# MultiTB.net
KiCad netlist of a schematic drawn in EAGLE
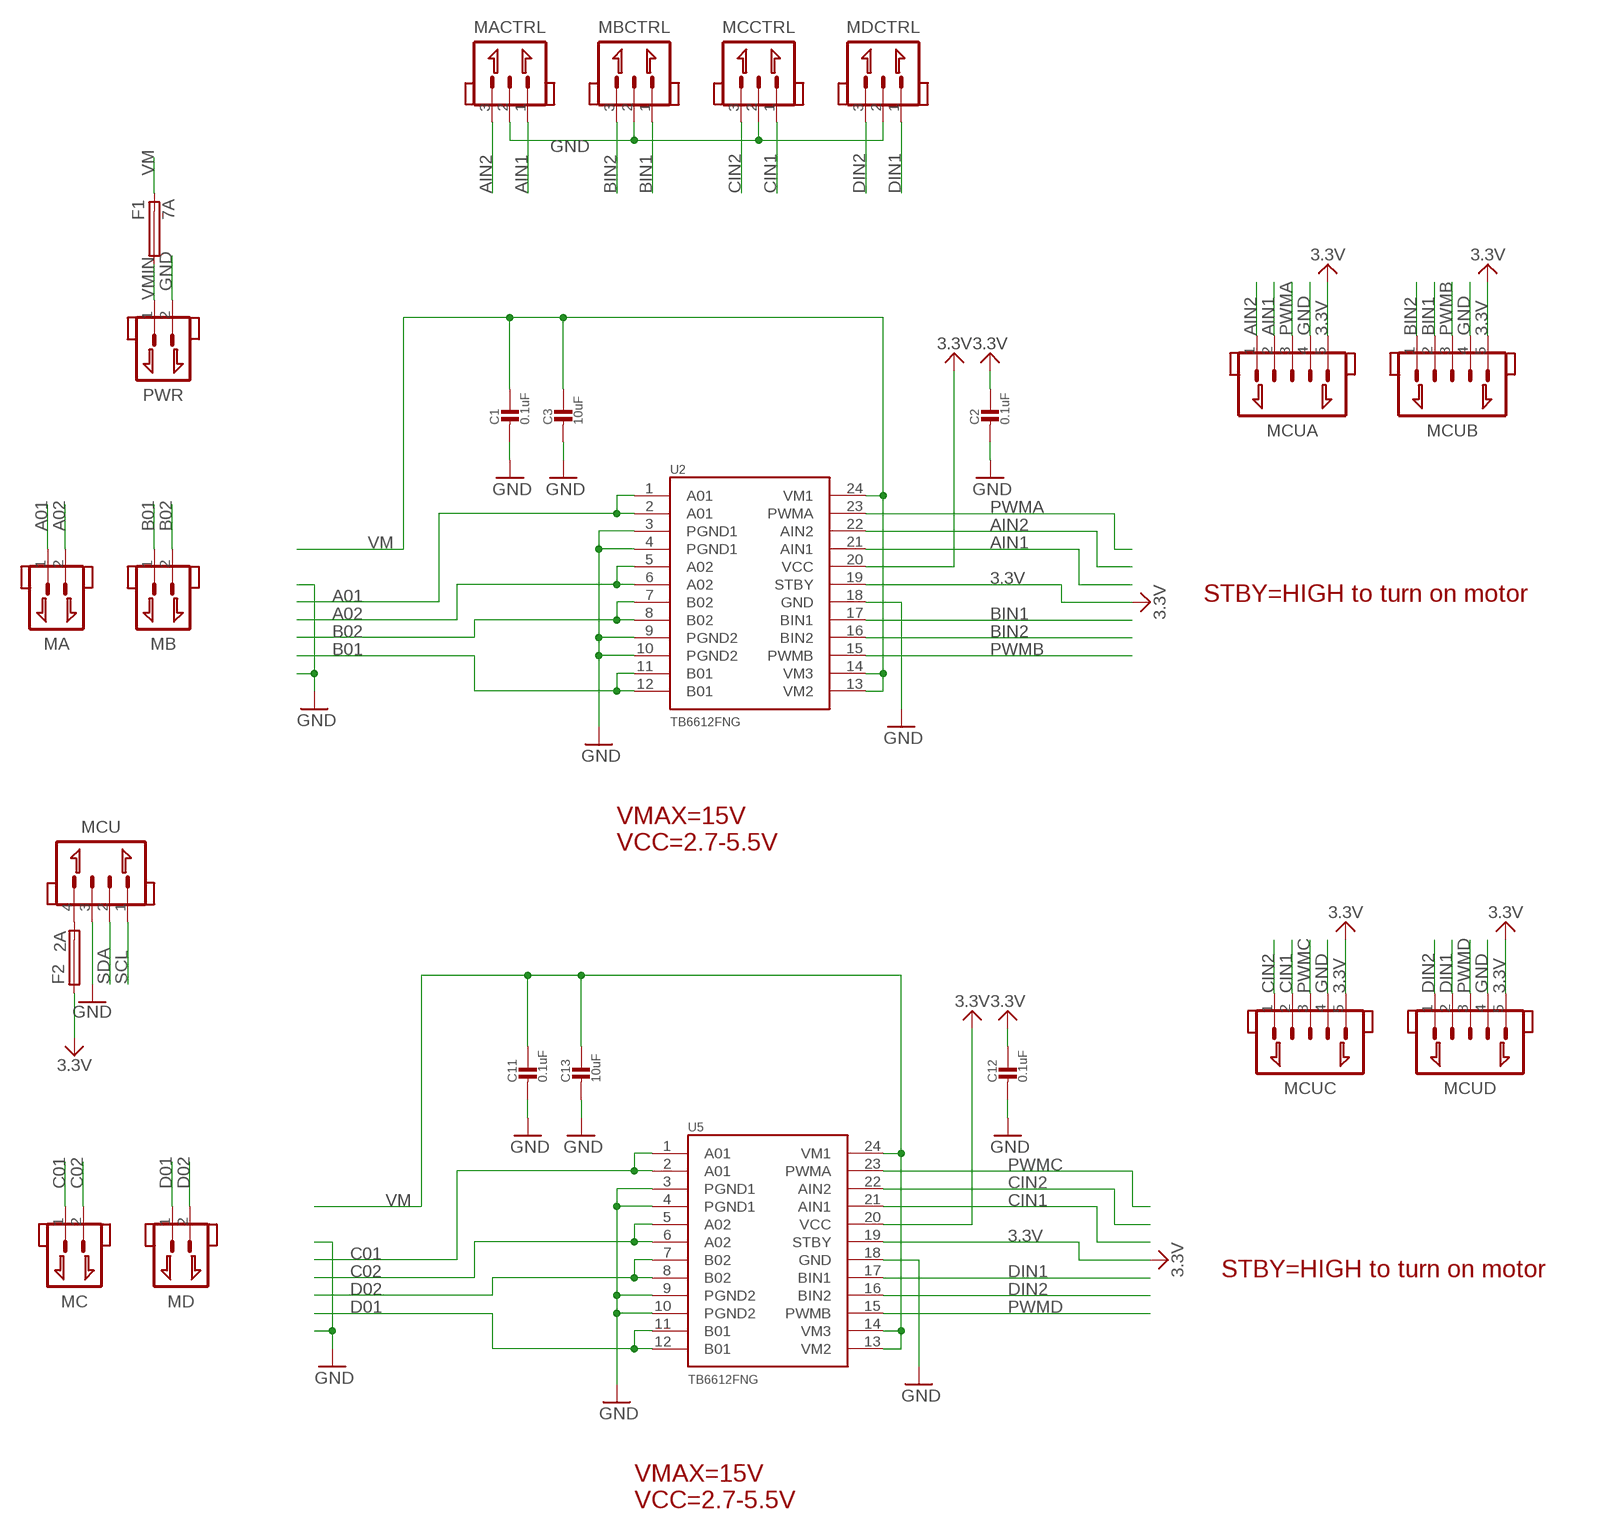
[diagram p0: schematic, sheet 1]
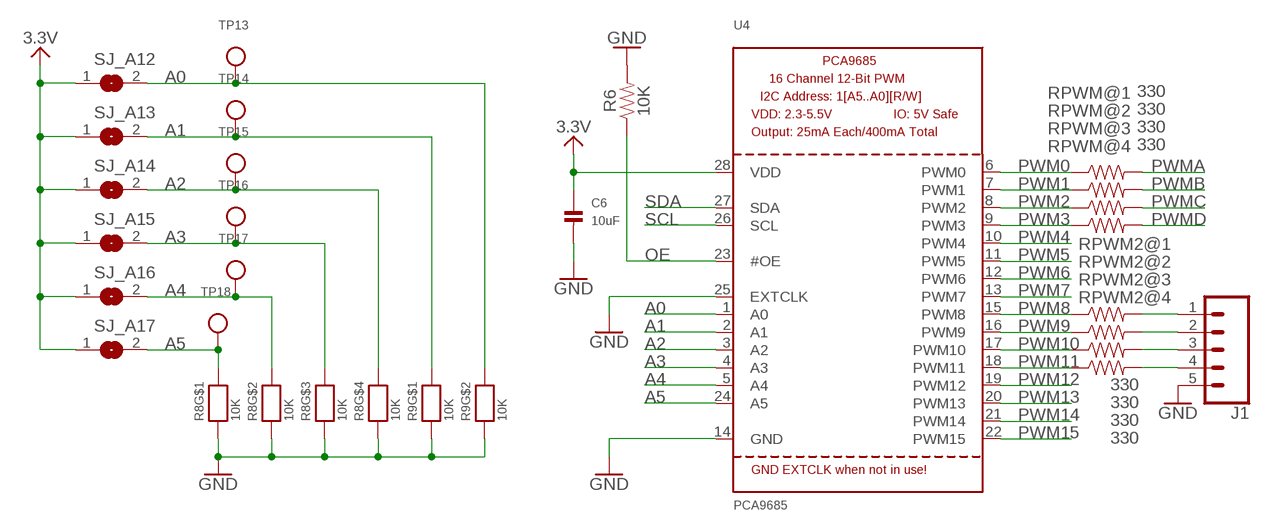
[diagram p1: schematic, sheet 2]

(export (version "E")
  (design (tool "Eeschema 10.0.6"))
  (components
    (comp (ref "C1")
      (value "0.1uF")
      (footprint "eagle-import:0603")
      (libsource (lib "eagle-import") (part "CAP_CERAMIC_0603"))
    )
    (comp (ref "C2")
      (value "0.1uF")
      (footprint "eagle-import:0603")
      (libsource (lib "eagle-import") (part "CAP_CERAMIC_0603"))
    )
    (comp (ref "C3")
      (value "10uF")
      (footprint "eagle-import:0805")
      (libsource (lib "eagle-import") (part "CAP_CERAMIC_0805"))
    )
    (comp (ref "C11")
      (value "0.1uF")
      (footprint "eagle-import:0603")
      (libsource (lib "eagle-import") (part "CAP_CERAMIC_0603"))
    )
    (comp (ref "C12")
      (value "0.1uF")
      (footprint "eagle-import:0603")
      (libsource (lib "eagle-import") (part "CAP_CERAMIC_0603"))
    )
    (comp (ref "C13")
      (value "10uF")
      (footprint "eagle-import:0805")
      (libsource (lib "eagle-import") (part "CAP_CERAMIC_0805"))
    )
    (comp (ref "F1")
      (value "7A")
      (footprint "eagle-import:1206")
      (libsource (lib "eagle-import") (part "FUSE-1206"))
    )
    (comp (ref "F2")
      (value "2A")
      (footprint "eagle-import:0603")
      (libsource (lib "eagle-import") (part "FUSE-0603"))
    )
    (comp (ref "MA")
      (value "JST_XH_2.54_2P")
      (footprint "eagle-import:JST_XH_2.54_2P")
      (libsource (lib "eagle-import") (part "JST_XH_2.54_2P"))
    )
    (comp (ref "MACTRL")
      (value "JST_1.25_3P")
      (footprint "eagle-import:JST1.25_3P")
      (libsource (lib "eagle-import") (part "JST_1.25_3P"))
    )
    (comp (ref "MB")
      (value "JST_XH_2.54_2P")
      (footprint "eagle-import:JST_XH_2.54_2P")
      (libsource (lib "eagle-import") (part "JST_XH_2.54_2P"))
    )
    (comp (ref "MBCTRL")
      (value "JST_1.25_3P")
      (footprint "eagle-import:JST1.25_3P")
      (libsource (lib "eagle-import") (part "JST_1.25_3P"))
    )
    (comp (ref "MC")
      (value "JST_XH_2.54_2P")
      (footprint "eagle-import:JST_XH_2.54_2P")
      (libsource (lib "eagle-import") (part "JST_XH_2.54_2P"))
    )
    (comp (ref "MCCTRL")
      (value "JST_1.25_3P")
      (footprint "eagle-import:JST1.25_3P")
      (libsource (lib "eagle-import") (part "JST_1.25_3P"))
    )
    (comp (ref "MCU")
      (value "JST_1.25_4P")
      (footprint "eagle-import:JST1.25_4P")
      (libsource (lib "eagle-import") (part "JST_1.25_4P"))
    )
    (comp (ref "MCUA")
      (value "JST_1.25_5P")
      (footprint "eagle-import:JST1.25_5P")
      (libsource (lib "eagle-import") (part "JST_1.25_5P"))
    )
    (comp (ref "MCUB")
      (value "JST_1.25_5P")
      (footprint "eagle-import:JST1.25_5P")
      (libsource (lib "eagle-import") (part "JST_1.25_5P"))
    )
    (comp (ref "MCUC")
      (value "JST_1.25_5P")
      (footprint "eagle-import:JST1.25_5P")
      (libsource (lib "eagle-import") (part "JST_1.25_5P"))
    )
    (comp (ref "MCUD")
      (value "JST_1.25_5P")
      (footprint "eagle-import:JST1.25_5P")
      (libsource (lib "eagle-import") (part "JST_1.25_5P"))
    )
    (comp (ref "MD")
      (value "JST_XH_2.54_2P")
      (footprint "eagle-import:JST_XH_2.54_2P")
      (libsource (lib "eagle-import") (part "JST_XH_2.54_2P"))
    )
    (comp (ref "MDCTRL")
      (value "JST_1.25_3P")
      (footprint "eagle-import:JST1.25_3P")
      (libsource (lib "eagle-import") (part "JST_1.25_3P"))
    )
    (comp (ref "PWR")
      (value "JST_XH_2.54_2P")
      (footprint "eagle-import:JST_XH_2.54_2P")
      (libsource (lib "eagle-import") (part "JST_XH_2.54_2P"))
    )
    (comp (ref "U2")
      (value "TB6612FNG")
      (footprint "eagle-import:SSOP24")
      (libsource (lib "eagle-import") (part "TB6612FNG"))
    )
    (comp (ref "U5")
      (value "TB6612FNG")
      (footprint "eagle-import:SSOP24")
      (libsource (lib "eagle-import") (part "TB6612FNG"))
    )
    (comp (ref "C6")
      (value "10uF")
      (footprint "eagle-import:0805")
      (libsource (lib "eagle-import") (part "CAP_CERAMIC_0805"))
    )
    (comp (ref "J1")
      (value "CONN_05")
      (footprint "eagle-import:1X05")
      (libsource (lib "eagle-import") (part "CONN_05"))
    )
    (comp (ref "R6")
      (value "10K")
      (footprint "eagle-import:0603")
      (libsource (lib "eagle-import") (part "RESISTOR0603"))
    )
    (comp (ref "R8")
      (value "10K")
      (footprint "eagle-import:RESPACK_4X0603")
      (libsource (lib "eagle-import") (part "RESISTOR_4PACK"))
    )
    (comp (ref "R9")
      (value "10K")
      (footprint "eagle-import:RESPACK_4X0603")
      (libsource (lib "eagle-import") (part "RESISTOR_4PACK"))
    )
    (comp (ref "RPWM")
      (value "330")
      (footprint "eagle-import:RESCAF80P320X160X60-8N")
      (libsource (lib "eagle-import") (part "RESISTOR_ARRAY_1206_SEPARATE_REVERSE"))
    )
    (comp (ref "RPWM2")
      (value "330")
      (footprint "eagle-import:RESCAF80P320X160X60-8N")
      (libsource (lib "eagle-import") (part "RESISTOR_ARRAY_1206_SEPARATE_REVERSE"))
    )
    (comp (ref "SJ_A12")
      (value "SOLDERJUMPERREFLOW_NOPASTE")
      (footprint "eagle-import:SOLDERJUMPER_REFLOW_NOPASTE")
      (libsource (lib "eagle-import") (part "SOLDERJUMPERREFLOW_NOPASTE"))
    )
    (comp (ref "SJ_A13")
      (value "SOLDERJUMPERREFLOW_NOPASTE")
      (footprint "eagle-import:SOLDERJUMPER_REFLOW_NOPASTE")
      (libsource (lib "eagle-import") (part "SOLDERJUMPERREFLOW_NOPASTE"))
    )
    (comp (ref "SJ_A14")
      (value "SOLDERJUMPERREFLOW_NOPASTE")
      (footprint "eagle-import:SOLDERJUMPER_REFLOW_NOPASTE")
      (libsource (lib "eagle-import") (part "SOLDERJUMPERREFLOW_NOPASTE"))
    )
    (comp (ref "SJ_A15")
      (value "SOLDERJUMPERREFLOW_NOPASTE")
      (footprint "eagle-import:SOLDERJUMPER_REFLOW_NOPASTE")
      (libsource (lib "eagle-import") (part "SOLDERJUMPERREFLOW_NOPASTE"))
    )
    (comp (ref "SJ_A16")
      (value "SOLDERJUMPERREFLOW_NOPASTE")
      (footprint "eagle-import:SOLDERJUMPER_REFLOW_NOPASTE")
      (libsource (lib "eagle-import") (part "SOLDERJUMPERREFLOW_NOPASTE"))
    )
    (comp (ref "SJ_A17")
      (value "SOLDERJUMPERREFLOW_NOPASTE")
      (footprint "eagle-import:SOLDERJUMPER_REFLOW_NOPASTE")
      (libsource (lib "eagle-import") (part "SOLDERJUMPERREFLOW_NOPASTE"))
    )
    (comp (ref "TP13")
      (value "TESTPOINTROUND2MM")
      (footprint "eagle-import:TESTPOINT_ROUND_2MM")
      (libsource (lib "eagle-import") (part "TESTPOINTROUND2MM"))
    )
    (comp (ref "TP14")
      (value "TESTPOINTROUND2MM")
      (footprint "eagle-import:TESTPOINT_ROUND_2MM")
      (libsource (lib "eagle-import") (part "TESTPOINTROUND2MM"))
    )
    (comp (ref "TP15")
      (value "TESTPOINTROUND2MM")
      (footprint "eagle-import:TESTPOINT_ROUND_2MM")
      (libsource (lib "eagle-import") (part "TESTPOINTROUND2MM"))
    )
    (comp (ref "TP16")
      (value "TESTPOINTROUND2MM")
      (footprint "eagle-import:TESTPOINT_ROUND_2MM")
      (libsource (lib "eagle-import") (part "TESTPOINTROUND2MM"))
    )
    (comp (ref "TP17")
      (value "TESTPOINTROUND2MM")
      (footprint "eagle-import:TESTPOINT_ROUND_2MM")
      (libsource (lib "eagle-import") (part "TESTPOINTROUND2MM"))
    )
    (comp (ref "TP18")
      (value "TESTPOINTROUND2MM")
      (footprint "eagle-import:TESTPOINT_ROUND_2MM")
      (libsource (lib "eagle-import") (part "TESTPOINTROUND2MM"))
    )
    (comp (ref "U4")
      (value "PCA9685")
      (footprint "eagle-import:TSSOP28")
      (libsource (lib "eagle-import") (part "PCA9685"))
    )
  )
  (nets
    (net (code "1") (name "3.3V") (class "Default")
      (node (ref "C12") (pin "1") (pinfunction "1_1") (pintype "passive"))
      (node (ref "C2") (pin "1") (pinfunction "1_1") (pintype "passive"))
      (node (ref "C6") (pin "1") (pinfunction "1_1") (pintype "passive"))
      (node (ref "F2") (pin "1") (pinfunction "1_1") (pintype "passive"))
      (node (ref "MCUA") (pin "5") (pinfunction "5_5") (pintype "passive"))
      (node (ref "MCUB") (pin "5") (pinfunction "5_5") (pintype "passive"))
      (node (ref "MCUC") (pin "5") (pinfunction "5_5") (pintype "passive"))
      (node (ref "MCUD") (pin "5") (pinfunction "5_5") (pintype "passive"))
      (node (ref "SJ_A12") (pin "1") (pinfunction "1_1") (pintype "passive"))
      (node (ref "SJ_A13") (pin "1") (pinfunction "1_1") (pintype "passive"))
      (node (ref "SJ_A14") (pin "1") (pinfunction "1_1") (pintype "passive"))
      (node (ref "SJ_A15") (pin "1") (pinfunction "1_1") (pintype "passive"))
      (node (ref "SJ_A16") (pin "1") (pinfunction "1_1") (pintype "passive"))
      (node (ref "SJ_A17") (pin "1") (pinfunction "1_1") (pintype "passive"))
      (node (ref "U2") (pin "19") (pinfunction "STBY_19") (pintype "bidirectional"))
      (node (ref "U2") (pin "20") (pinfunction "VCC_20") (pintype "bidirectional"))
      (node (ref "U4") (pin "28") (pinfunction "VDD_28") (pintype "power_in"))
      (node (ref "U5") (pin "19") (pinfunction "STBY_19") (pintype "bidirectional"))
      (node (ref "U5") (pin "20") (pinfunction "VCC_20") (pintype "bidirectional"))
    )
    (net (code "2") (name "A0") (class "Default")
      (node (ref "R9") (pin "7") (pinfunction "2_7") (pintype "passive"))
      (node (ref "SJ_A12") (pin "2") (pinfunction "2_2") (pintype "passive"))
      (node (ref "TP13") (pin "P$1") (pinfunction "P$1_P$1") (pintype "bidirectional"))
      (node (ref "U4") (pin "1") (pinfunction "A0_1") (pintype "bidirectional"))
    )
    (net (code "3") (name "A1") (class "Default")
      (node (ref "R9") (pin "8") (pinfunction "2_8") (pintype "passive"))
      (node (ref "SJ_A13") (pin "2") (pinfunction "2_2") (pintype "passive"))
      (node (ref "TP14") (pin "P$1") (pinfunction "P$1_P$1") (pintype "bidirectional"))
      (node (ref "U4") (pin "2") (pinfunction "A1_2") (pintype "bidirectional"))
    )
    (net (code "4") (name "A01") (class "Default")
      (node (ref "MA") (pin "1") (pinfunction "1_1") (pintype "passive"))
      (node (ref "U2") (pin "1") (pinfunction "A01_1") (pintype "bidirectional"))
      (node (ref "U2") (pin "2") (pinfunction "A01_2") (pintype "bidirectional"))
    )
    (net (code "5") (name "A2") (class "Default")
      (node (ref "R8") (pin "5") (pinfunction "2_5") (pintype "passive"))
      (node (ref "SJ_A14") (pin "2") (pinfunction "2_2") (pintype "passive"))
      (node (ref "TP15") (pin "P$1") (pinfunction "P$1_P$1") (pintype "bidirectional"))
      (node (ref "U4") (pin "3") (pinfunction "A2_3") (pintype "bidirectional"))
    )
    (net (code "6") (name "A02") (class "Default")
      (node (ref "MA") (pin "2") (pinfunction "2_2") (pintype "passive"))
      (node (ref "U2") (pin "5") (pinfunction "A02_5") (pintype "bidirectional"))
      (node (ref "U2") (pin "6") (pinfunction "A02_6") (pintype "bidirectional"))
    )
    (net (code "7") (name "A3") (class "Default")
      (node (ref "R8") (pin "6") (pinfunction "2_6") (pintype "passive"))
      (node (ref "SJ_A15") (pin "2") (pinfunction "2_2") (pintype "passive"))
      (node (ref "TP16") (pin "P$1") (pinfunction "P$1_P$1") (pintype "bidirectional"))
      (node (ref "U4") (pin "4") (pinfunction "A3_4") (pintype "bidirectional"))
    )
    (net (code "8") (name "A4") (class "Default")
      (node (ref "R8") (pin "7") (pinfunction "2_7") (pintype "passive"))
      (node (ref "SJ_A16") (pin "2") (pinfunction "2_2") (pintype "passive"))
      (node (ref "TP17") (pin "P$1") (pinfunction "P$1_P$1") (pintype "bidirectional"))
      (node (ref "U4") (pin "5") (pinfunction "A4_5") (pintype "bidirectional"))
    )
    (net (code "9") (name "A5") (class "Default")
      (node (ref "R8") (pin "8") (pinfunction "2_8") (pintype "passive"))
      (node (ref "SJ_A17") (pin "2") (pinfunction "2_2") (pintype "passive"))
      (node (ref "TP18") (pin "P$1") (pinfunction "P$1_P$1") (pintype "bidirectional"))
      (node (ref "U4") (pin "24") (pinfunction "A5_24") (pintype "bidirectional"))
    )
    (net (code "10") (name "AIN1") (class "Default")
      (node (ref "MACTRL") (pin "1") (pinfunction "1_1") (pintype "passive"))
      (node (ref "MCUA") (pin "2") (pinfunction "2_2") (pintype "passive"))
      (node (ref "U2") (pin "21") (pinfunction "AIN1_21") (pintype "bidirectional"))
    )
    (net (code "11") (name "AIN2") (class "Default")
      (node (ref "MACTRL") (pin "3") (pinfunction "3_3") (pintype "passive"))
      (node (ref "MCUA") (pin "1") (pinfunction "1_1") (pintype "passive"))
      (node (ref "U2") (pin "22") (pinfunction "AIN2_22") (pintype "bidirectional"))
    )
    (net (code "12") (name "B01") (class "Default")
      (node (ref "MB") (pin "1") (pinfunction "1_1") (pintype "passive"))
      (node (ref "U2") (pin "11") (pinfunction "B01_11") (pintype "bidirectional"))
      (node (ref "U2") (pin "12") (pinfunction "B01_12") (pintype "bidirectional"))
    )
    (net (code "13") (name "B02") (class "Default")
      (node (ref "MB") (pin "2") (pinfunction "2_2") (pintype "passive"))
      (node (ref "U2") (pin "7") (pinfunction "B02_7") (pintype "bidirectional"))
      (node (ref "U2") (pin "8") (pinfunction "B02_8") (pintype "bidirectional"))
    )
    (net (code "14") (name "BIN1") (class "Default")
      (node (ref "MBCTRL") (pin "1") (pinfunction "1_1") (pintype "passive"))
      (node (ref "MCUB") (pin "2") (pinfunction "2_2") (pintype "passive"))
      (node (ref "U2") (pin "17") (pinfunction "BIN1_17") (pintype "bidirectional"))
    )
    (net (code "15") (name "BIN2") (class "Default")
      (node (ref "MBCTRL") (pin "3") (pinfunction "3_3") (pintype "passive"))
      (node (ref "MCUB") (pin "1") (pinfunction "1_1") (pintype "passive"))
      (node (ref "U2") (pin "16") (pinfunction "BIN2_16") (pintype "bidirectional"))
    )
    (net (code "16") (name "C01") (class "Default")
      (node (ref "MC") (pin "1") (pinfunction "1_1") (pintype "passive"))
      (node (ref "U5") (pin "1") (pinfunction "A01_1") (pintype "bidirectional"))
      (node (ref "U5") (pin "2") (pinfunction "A01_2") (pintype "bidirectional"))
    )
    (net (code "17") (name "C02") (class "Default")
      (node (ref "MC") (pin "2") (pinfunction "2_2") (pintype "passive"))
      (node (ref "U5") (pin "5") (pinfunction "A02_5") (pintype "bidirectional"))
      (node (ref "U5") (pin "6") (pinfunction "A02_6") (pintype "bidirectional"))
    )
    (net (code "18") (name "CIN1") (class "Default")
      (node (ref "MCCTRL") (pin "1") (pinfunction "1_1") (pintype "passive"))
      (node (ref "MCUC") (pin "2") (pinfunction "2_2") (pintype "passive"))
      (node (ref "U5") (pin "21") (pinfunction "AIN1_21") (pintype "bidirectional"))
    )
    (net (code "19") (name "CIN2") (class "Default")
      (node (ref "MCCTRL") (pin "3") (pinfunction "3_3") (pintype "passive"))
      (node (ref "MCUC") (pin "1") (pinfunction "1_1") (pintype "passive"))
      (node (ref "U5") (pin "22") (pinfunction "AIN2_22") (pintype "bidirectional"))
    )
    (net (code "20") (name "D01") (class "Default")
      (node (ref "MD") (pin "1") (pinfunction "1_1") (pintype "passive"))
      (node (ref "U5") (pin "11") (pinfunction "B01_11") (pintype "bidirectional"))
      (node (ref "U5") (pin "12") (pinfunction "B01_12") (pintype "bidirectional"))
    )
    (net (code "21") (name "D02") (class "Default")
      (node (ref "MD") (pin "2") (pinfunction "2_2") (pintype "passive"))
      (node (ref "U5") (pin "7") (pinfunction "B02_7") (pintype "bidirectional"))
      (node (ref "U5") (pin "8") (pinfunction "B02_8") (pintype "bidirectional"))
    )
    (net (code "22") (name "DIN1") (class "Default")
      (node (ref "MCUD") (pin "2") (pinfunction "2_2") (pintype "passive"))
      (node (ref "MDCTRL") (pin "1") (pinfunction "1_1") (pintype "passive"))
      (node (ref "U5") (pin "17") (pinfunction "BIN1_17") (pintype "bidirectional"))
    )
    (net (code "23") (name "DIN2") (class "Default")
      (node (ref "MCUD") (pin "1") (pinfunction "1_1") (pintype "passive"))
      (node (ref "MDCTRL") (pin "3") (pinfunction "3_3") (pintype "passive"))
      (node (ref "U5") (pin "16") (pinfunction "BIN2_16") (pintype "bidirectional"))
    )
    (net (code "24") (name "GND") (class "Default")
      (node (ref "C1") (pin "2") (pinfunction "2_2") (pintype "passive"))
      (node (ref "C11") (pin "2") (pinfunction "2_2") (pintype "passive"))
      (node (ref "C12") (pin "2") (pinfunction "2_2") (pintype "passive"))
      (node (ref "C13") (pin "2") (pinfunction "2_2") (pintype "passive"))
      (node (ref "C2") (pin "2") (pinfunction "2_2") (pintype "passive"))
      (node (ref "C3") (pin "2") (pinfunction "2_2") (pintype "passive"))
      (node (ref "C6") (pin "2") (pinfunction "2_2") (pintype "passive"))
      (node (ref "J1") (pin "5") (pinfunction "5_5") (pintype "passive"))
      (node (ref "MACTRL") (pin "2") (pinfunction "2_2") (pintype "passive"))
      (node (ref "MBCTRL") (pin "2") (pinfunction "2_2") (pintype "passive"))
      (node (ref "MCCTRL") (pin "2") (pinfunction "2_2") (pintype "passive"))
      (node (ref "MCU") (pin "3") (pinfunction "3_3") (pintype "passive"))
      (node (ref "MCUA") (pin "4") (pinfunction "4_4") (pintype "passive"))
      (node (ref "MCUB") (pin "4") (pinfunction "4_4") (pintype "passive"))
      (node (ref "MCUC") (pin "4") (pinfunction "4_4") (pintype "passive"))
      (node (ref "MCUD") (pin "4") (pinfunction "4_4") (pintype "passive"))
      (node (ref "MDCTRL") (pin "2") (pinfunction "2_2") (pintype "passive"))
      (node (ref "PWR") (pin "2") (pinfunction "2_2") (pintype "passive"))
      (node (ref "R6") (pin "2") (pinfunction "2_2") (pintype "passive"))
      (node (ref "R8") (pin "1") (pinfunction "1_1") (pintype "passive"))
      (node (ref "R8") (pin "2") (pinfunction "1_2") (pintype "passive"))
      (node (ref "R8") (pin "3") (pinfunction "1_3") (pintype "passive"))
      (node (ref "R8") (pin "4") (pinfunction "1_4") (pintype "passive"))
      (node (ref "R9") (pin "1") (pinfunction "1_1") (pintype "passive"))
      (node (ref "R9") (pin "2") (pinfunction "1_2") (pintype "passive"))
      (node (ref "U2") (pin "10") (pinfunction "PGND2_10") (pintype "bidirectional"))
      (node (ref "U2") (pin "18") (pinfunction "GND_18") (pintype "bidirectional"))
      (node (ref "U2") (pin "3") (pinfunction "PGND1_3") (pintype "bidirectional"))
      (node (ref "U2") (pin "4") (pinfunction "PGND1_4") (pintype "bidirectional"))
      (node (ref "U2") (pin "9") (pinfunction "PGND2_9") (pintype "bidirectional"))
      (node (ref "U4") (pin "14") (pinfunction "GND_14") (pintype "power_in"))
      (node (ref "U4") (pin "25") (pinfunction "EXTCLK_25") (pintype "input"))
      (node (ref "U5") (pin "10") (pinfunction "PGND2_10") (pintype "bidirectional"))
      (node (ref "U5") (pin "18") (pinfunction "GND_18") (pintype "bidirectional"))
      (node (ref "U5") (pin "3") (pinfunction "PGND1_3") (pintype "bidirectional"))
      (node (ref "U5") (pin "4") (pinfunction "PGND1_4") (pintype "bidirectional"))
      (node (ref "U5") (pin "9") (pinfunction "PGND2_9") (pintype "bidirectional"))
    )
    (net (code "25") (name "Net-(F2-Pad2)") (class "Default")
      (node (ref "F2") (pin "2") (pinfunction "2_2") (pintype "passive"))
      (node (ref "MCU") (pin "4") (pinfunction "4_4") (pintype "passive"))
    )
    (net (code "26") (name "Net-(J1-Pad2)") (class "Default")
      (node (ref "J1") (pin "2") (pinfunction "2_2") (pintype "passive"))
      (node (ref "RPWM2") (pin "2") (pinfunction "2_2") (pintype "passive"))
    )
    (net (code "27") (name "Net-(RPWM2A-2)") (class "Default")
      (node (ref "J1") (pin "1") (pinfunction "1_1") (pintype "passive"))
      (node (ref "RPWM2") (pin "1") (pinfunction "2_1") (pintype "passive"))
    )
    (net (code "28") (name "Net-(RPWM2C-2)") (class "Default")
      (node (ref "J1") (pin "3") (pinfunction "3_3") (pintype "passive"))
      (node (ref "RPWM2") (pin "3") (pinfunction "2_3") (pintype "passive"))
    )
    (net (code "29") (name "Net-(RPWM2D-2)") (class "Default")
      (node (ref "J1") (pin "4") (pinfunction "4_4") (pintype "passive"))
      (node (ref "RPWM2") (pin "4") (pinfunction "2_4") (pintype "passive"))
    )
    (net (code "30") (name "OE") (class "Default")
      (node (ref "R6") (pin "1") (pinfunction "1_1") (pintype "passive"))
      (node (ref "U4") (pin "23") (pinfunction "#OE_23") (pintype "input"))
    )
    (net (code "31") (name "PWM0") (class "Default")
      (node (ref "RPWM") (pin "8") (pinfunction "1_8") (pintype "passive"))
      (node (ref "U4") (pin "6") (pinfunction "PWM0_6") (pintype "output"))
    )
    (net (code "32") (name "PWM1") (class "Default")
      (node (ref "RPWM") (pin "7") (pinfunction "1_7") (pintype "passive"))
      (node (ref "U4") (pin "7") (pinfunction "PWM1_7") (pintype "output"))
    )
    (net (code "33") (name "PWM2") (class "Default")
      (node (ref "RPWM") (pin "6") (pinfunction "1_6") (pintype "passive"))
      (node (ref "U4") (pin "8") (pinfunction "PWM2_8") (pintype "output"))
    )
    (net (code "34") (name "PWM3") (class "Default")
      (node (ref "RPWM") (pin "5") (pinfunction "1_5") (pintype "passive"))
      (node (ref "U4") (pin "9") (pinfunction "PWM3_9") (pintype "output"))
    )
    (net (code "35") (name "PWM4") (class "Default")
      (node (ref "U4") (pin "10") (pinfunction "PWM4_10") (pintype "output"))
    )
    (net (code "36") (name "PWM5") (class "Default")
      (node (ref "U4") (pin "11") (pinfunction "PWM5_11") (pintype "output"))
    )
    (net (code "37") (name "PWM6") (class "Default")
      (node (ref "U4") (pin "12") (pinfunction "PWM6_12") (pintype "output"))
    )
    (net (code "38") (name "PWM7") (class "Default")
      (node (ref "U4") (pin "13") (pinfunction "PWM7_13") (pintype "output"))
    )
    (net (code "39") (name "PWM8") (class "Default")
      (node (ref "RPWM2") (pin "8") (pinfunction "1_8") (pintype "passive"))
      (node (ref "U4") (pin "15") (pinfunction "PWM8_15") (pintype "output"))
    )
    (net (code "40") (name "PWM9") (class "Default")
      (node (ref "RPWM2") (pin "7") (pinfunction "1_7") (pintype "passive"))
      (node (ref "U4") (pin "16") (pinfunction "PWM9_16") (pintype "output"))
    )
    (net (code "41") (name "PWM10") (class "Default")
      (node (ref "RPWM2") (pin "6") (pinfunction "1_6") (pintype "passive"))
      (node (ref "U4") (pin "17") (pinfunction "PWM10_17") (pintype "output"))
    )
    (net (code "42") (name "PWM11") (class "Default")
      (node (ref "RPWM2") (pin "5") (pinfunction "1_5") (pintype "passive"))
      (node (ref "U4") (pin "18") (pinfunction "PWM11_18") (pintype "output"))
    )
    (net (code "43") (name "PWM12") (class "Default")
      (node (ref "U4") (pin "19") (pinfunction "PWM12_19") (pintype "output"))
    )
    (net (code "44") (name "PWM13") (class "Default")
      (node (ref "U4") (pin "20") (pinfunction "PWM13_20") (pintype "output"))
    )
    (net (code "45") (name "PWM14") (class "Default")
      (node (ref "U4") (pin "21") (pinfunction "PWM14_21") (pintype "output"))
    )
    (net (code "46") (name "PWM15") (class "Default")
      (node (ref "U4") (pin "22") (pinfunction "PWM15_22") (pintype "output"))
    )
    (net (code "47") (name "PWMA") (class "Default")
      (node (ref "MCUA") (pin "3") (pinfunction "3_3") (pintype "passive"))
      (node (ref "RPWM") (pin "1") (pinfunction "2_1") (pintype "passive"))
      (node (ref "U2") (pin "23") (pinfunction "PWMA_23") (pintype "bidirectional"))
    )
    (net (code "48") (name "PWMB") (class "Default")
      (node (ref "MCUB") (pin "3") (pinfunction "3_3") (pintype "passive"))
      (node (ref "RPWM") (pin "2") (pinfunction "2_2") (pintype "passive"))
      (node (ref "U2") (pin "15") (pinfunction "PWMB_15") (pintype "bidirectional"))
    )
    (net (code "49") (name "PWMC") (class "Default")
      (node (ref "MCUC") (pin "3") (pinfunction "3_3") (pintype "passive"))
      (node (ref "RPWM") (pin "3") (pinfunction "2_3") (pintype "passive"))
      (node (ref "U5") (pin "23") (pinfunction "PWMA_23") (pintype "bidirectional"))
    )
    (net (code "50") (name "PWMD") (class "Default")
      (node (ref "MCUD") (pin "3") (pinfunction "3_3") (pintype "passive"))
      (node (ref "RPWM") (pin "4") (pinfunction "2_4") (pintype "passive"))
      (node (ref "U5") (pin "15") (pinfunction "PWMB_15") (pintype "bidirectional"))
    )
    (net (code "51") (name "SCL") (class "Default")
      (node (ref "MCU") (pin "1") (pinfunction "1_1") (pintype "passive"))
      (node (ref "U4") (pin "26") (pinfunction "SCL_26") (pintype "bidirectional"))
    )
    (net (code "52") (name "SDA") (class "Default")
      (node (ref "MCU") (pin "2") (pinfunction "2_2") (pintype "passive"))
      (node (ref "U4") (pin "27") (pinfunction "SDA_27") (pintype "bidirectional"))
    )
    (net (code "53") (name "VM") (class "Default")
      (node (ref "C1") (pin "1") (pinfunction "1_1") (pintype "passive"))
      (node (ref "C11") (pin "1") (pinfunction "1_1") (pintype "passive"))
      (node (ref "C13") (pin "1") (pinfunction "1_1") (pintype "passive"))
      (node (ref "C3") (pin "1") (pinfunction "1_1") (pintype "passive"))
      (node (ref "F1") (pin "2") (pinfunction "2_2") (pintype "passive"))
      (node (ref "U2") (pin "13") (pinfunction "VM2_13") (pintype "bidirectional"))
      (node (ref "U2") (pin "14") (pinfunction "VM3_14") (pintype "bidirectional"))
      (node (ref "U2") (pin "24") (pinfunction "VM1_24") (pintype "bidirectional"))
      (node (ref "U5") (pin "13") (pinfunction "VM2_13") (pintype "bidirectional"))
      (node (ref "U5") (pin "14") (pinfunction "VM3_14") (pintype "bidirectional"))
      (node (ref "U5") (pin "24") (pinfunction "VM1_24") (pintype "bidirectional"))
    )
    (net (code "54") (name "VMIN") (class "Default")
      (node (ref "F1") (pin "1") (pinfunction "1_1") (pintype "passive"))
      (node (ref "PWR") (pin "1") (pinfunction "1_1") (pintype "passive"))
    )
  )
)
